# hw6.net
KiCad netlist of a schematic drawn in EAGLE
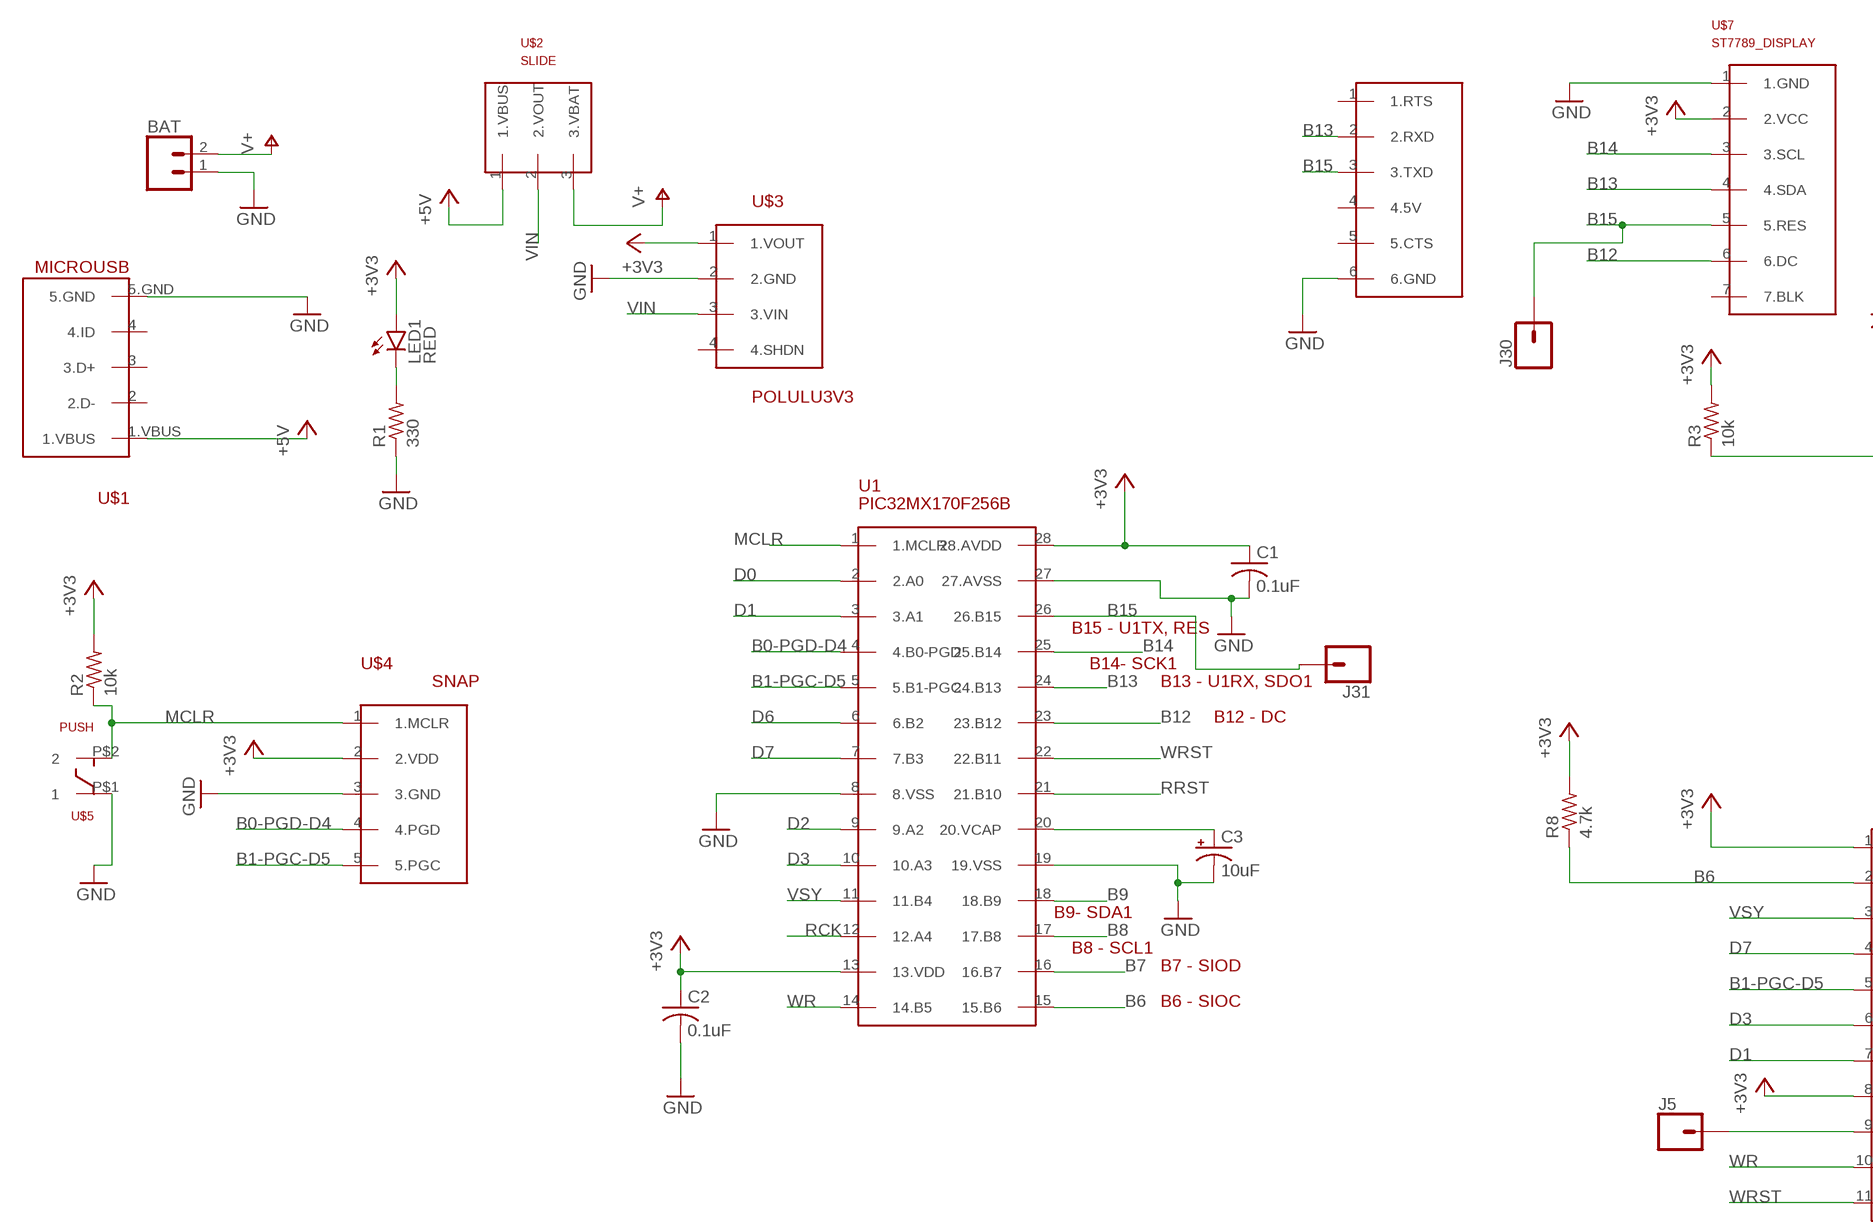
[diagram p0: schematic, sheet 1, part 1 of 2]
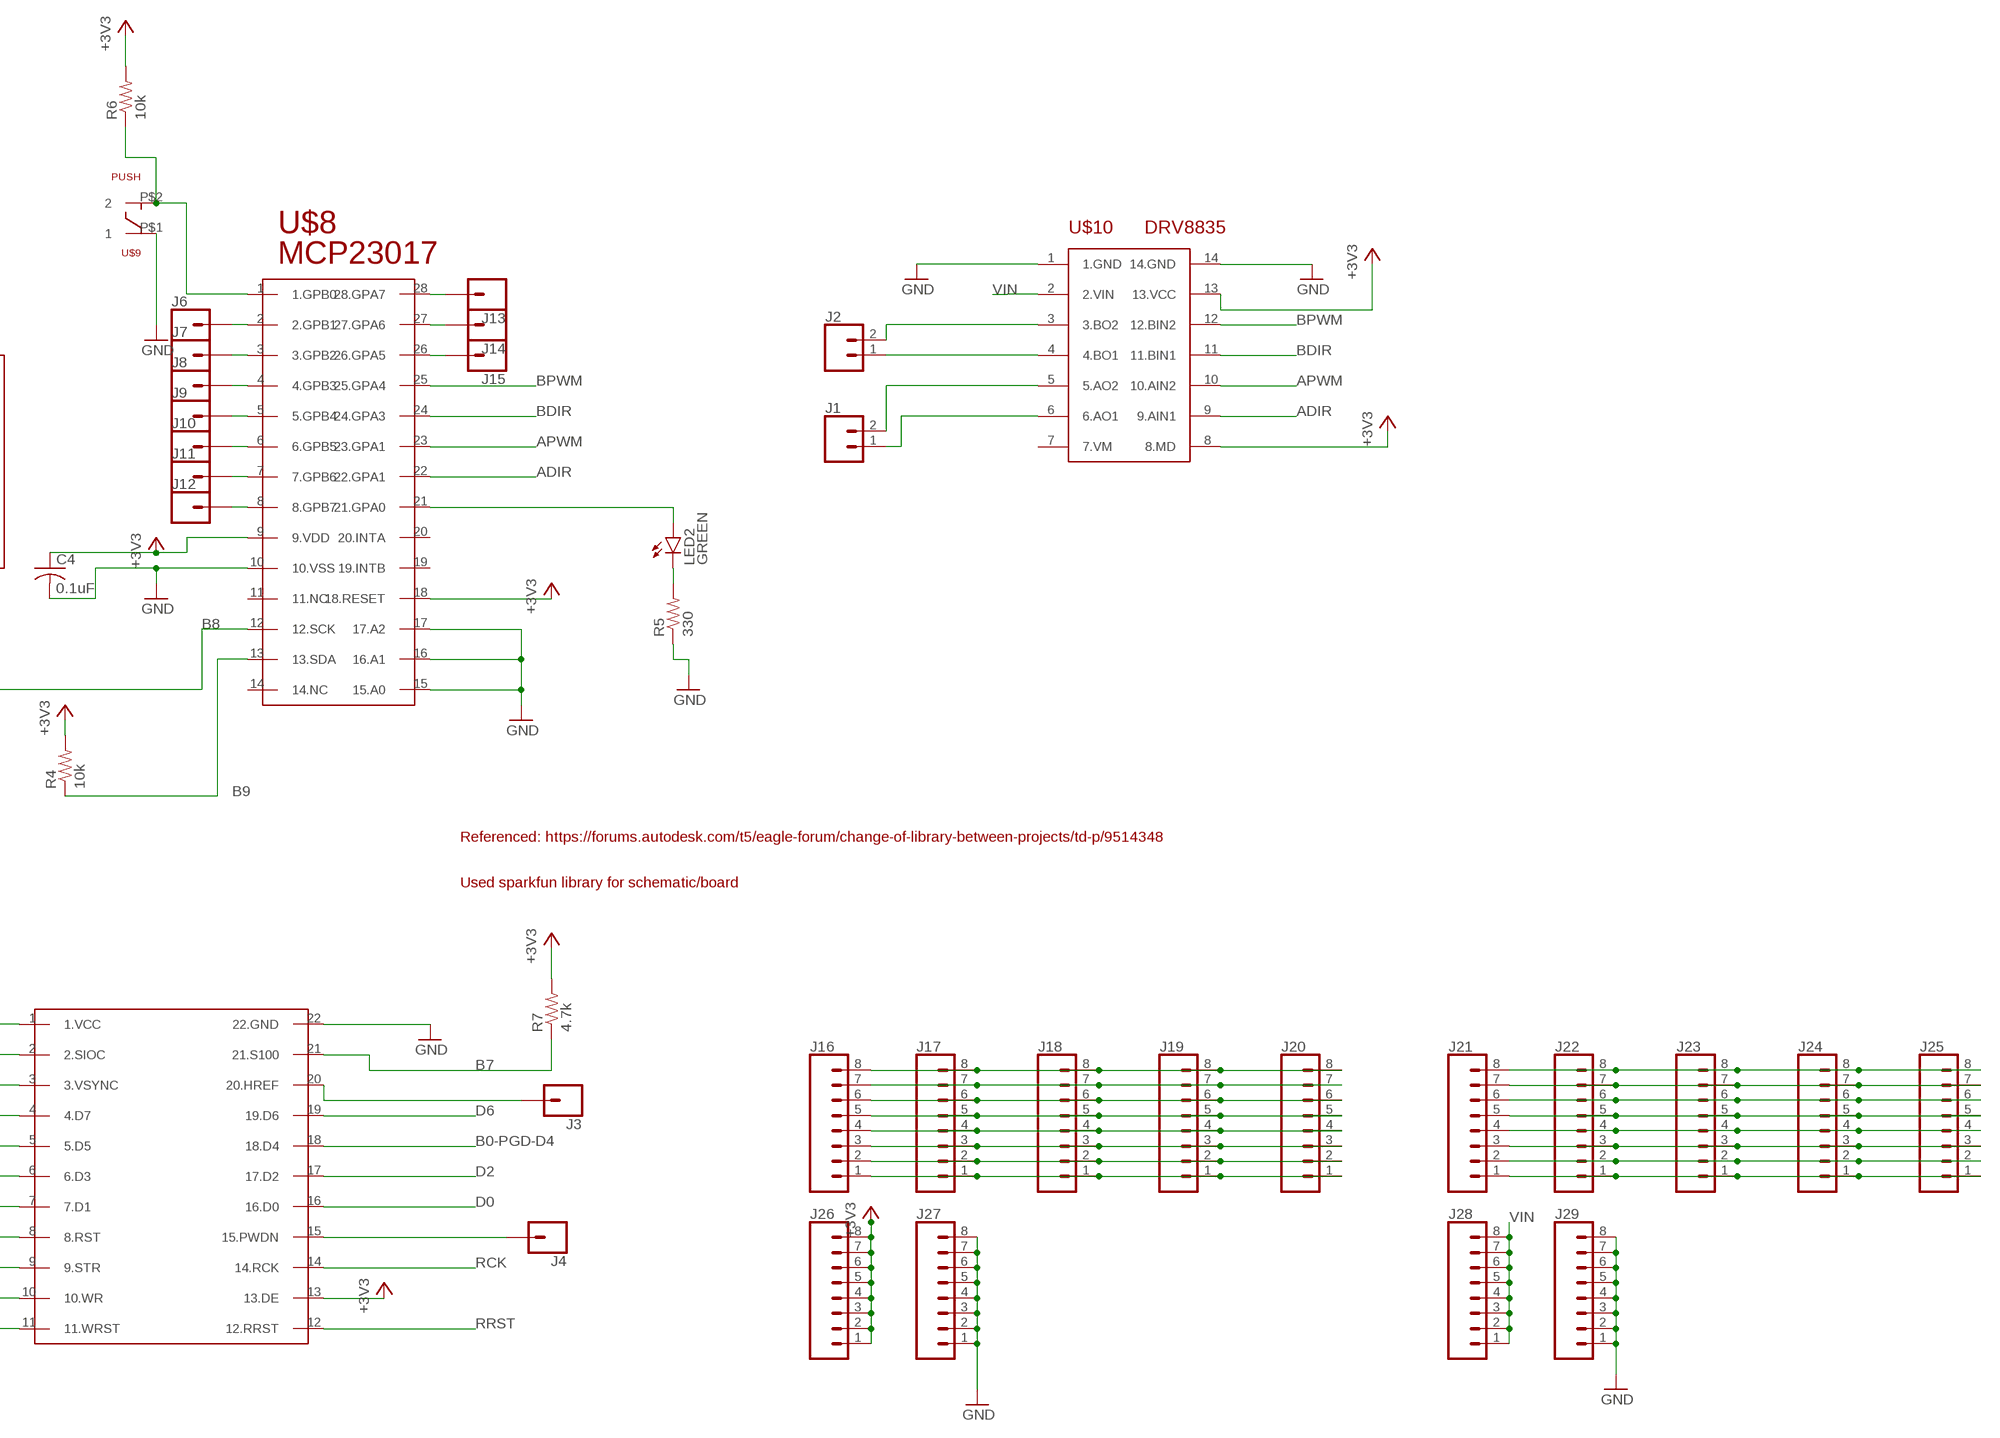
[diagram p1: schematic, sheet 1, part 2 of 2]

(export (version "E")
  (design (tool "Eeschema 10.0.6"))
  (components
    (comp (ref "BAT")
      (value "CONN_02")
      (footprint "eagle-import:1X02")
      (libsource (lib "eagle-import") (part "CONN_02"))
    )
    (comp (ref "C1")
      (value "0.1uF")
      (footprint "eagle-import:C025-030X050")
      (libsource (lib "eagle-import") (part "C-US025-030X050"))
    )
    (comp (ref "C2")
      (value "0.1uF")
      (footprint "eagle-import:C025-030X050")
      (libsource (lib "eagle-import") (part "C-US025-030X050"))
    )
    (comp (ref "C3")
      (value "10uF")
      (footprint "eagle-import:B45181B")
      (libsource (lib "eagle-import") (part "CPOL-USB45181B"))
    )
    (comp (ref "C4")
      (value "0.1uF")
      (footprint "eagle-import:C025-030X050")
      (libsource (lib "eagle-import") (part "C-US025-030X050"))
    )
    (comp (ref "J1")
      (value "CONN_02")
      (footprint "eagle-import:1X02")
      (libsource (lib "eagle-import") (part "CONN_02"))
    )
    (comp (ref "J2")
      (value "CONN_02")
      (footprint "eagle-import:1X02")
      (libsource (lib "eagle-import") (part "CONN_02"))
    )
    (comp (ref "J3")
      (value "CONN_01")
      (footprint "eagle-import:1X01")
      (libsource (lib "eagle-import") (part "CONN_01"))
    )
    (comp (ref "J4")
      (value "CONN_01")
      (footprint "eagle-import:1X01")
      (libsource (lib "eagle-import") (part "CONN_01"))
    )
    (comp (ref "J5")
      (value "CONN_01")
      (footprint "eagle-import:1X01")
      (libsource (lib "eagle-import") (part "CONN_01"))
    )
    (comp (ref "J6")
      (value "CONN_01")
      (footprint "eagle-import:1X01")
      (libsource (lib "eagle-import") (part "CONN_01"))
    )
    (comp (ref "J7")
      (value "CONN_01")
      (footprint "eagle-import:1X01")
      (libsource (lib "eagle-import") (part "CONN_01"))
    )
    (comp (ref "J8")
      (value "CONN_01")
      (footprint "eagle-import:1X01")
      (libsource (lib "eagle-import") (part "CONN_01"))
    )
    (comp (ref "J9")
      (value "CONN_01")
      (footprint "eagle-import:1X01")
      (libsource (lib "eagle-import") (part "CONN_01"))
    )
    (comp (ref "J10")
      (value "CONN_01")
      (footprint "eagle-import:1X01")
      (libsource (lib "eagle-import") (part "CONN_01"))
    )
    (comp (ref "J11")
      (value "CONN_01")
      (footprint "eagle-import:1X01")
      (libsource (lib "eagle-import") (part "CONN_01"))
    )
    (comp (ref "J12")
      (value "CONN_01")
      (footprint "eagle-import:1X01")
      (libsource (lib "eagle-import") (part "CONN_01"))
    )
    (comp (ref "J13")
      (value "CONN_01")
      (footprint "eagle-import:1X01")
      (libsource (lib "eagle-import") (part "CONN_01"))
    )
    (comp (ref "J14")
      (value "CONN_01")
      (footprint "eagle-import:1X01")
      (libsource (lib "eagle-import") (part "CONN_01"))
    )
    (comp (ref "J15")
      (value "CONN_01")
      (footprint "eagle-import:1X01")
      (libsource (lib "eagle-import") (part "CONN_01"))
    )
    (comp (ref "J16")
      (value "CONN_08\"")
      (footprint "eagle-import:1X08")
      (libsource (lib "eagle-import") (part "CONN_08{dblquote}"))
    )
    (comp (ref "J17")
      (value "CONN_08\"")
      (footprint "eagle-import:1X08")
      (libsource (lib "eagle-import") (part "CONN_08{dblquote}"))
    )
    (comp (ref "J18")
      (value "CONN_08\"")
      (footprint "eagle-import:1X08")
      (libsource (lib "eagle-import") (part "CONN_08{dblquote}"))
    )
    (comp (ref "J19")
      (value "CONN_08\"")
      (footprint "eagle-import:1X08")
      (libsource (lib "eagle-import") (part "CONN_08{dblquote}"))
    )
    (comp (ref "J20")
      (value "CONN_08\"")
      (footprint "eagle-import:1X08")
      (libsource (lib "eagle-import") (part "CONN_08{dblquote}"))
    )
    (comp (ref "J21")
      (value "CONN_08\"")
      (footprint "eagle-import:1X08")
      (libsource (lib "eagle-import") (part "CONN_08{dblquote}"))
    )
    (comp (ref "J22")
      (value "CONN_08\"")
      (footprint "eagle-import:1X08")
      (libsource (lib "eagle-import") (part "CONN_08{dblquote}"))
    )
    (comp (ref "J23")
      (value "CONN_08\"")
      (footprint "eagle-import:1X08")
      (libsource (lib "eagle-import") (part "CONN_08{dblquote}"))
    )
    (comp (ref "J24")
      (value "CONN_08\"")
      (footprint "eagle-import:1X08")
      (libsource (lib "eagle-import") (part "CONN_08{dblquote}"))
    )
    (comp (ref "J25")
      (value "CONN_08\"")
      (footprint "eagle-import:1X08")
      (libsource (lib "eagle-import") (part "CONN_08{dblquote}"))
    )
    (comp (ref "J26")
      (value "CONN_08\"")
      (footprint "eagle-import:1X08")
      (libsource (lib "eagle-import") (part "CONN_08{dblquote}"))
    )
    (comp (ref "J27")
      (value "CONN_08\"")
      (footprint "eagle-import:1X08")
      (libsource (lib "eagle-import") (part "CONN_08{dblquote}"))
    )
    (comp (ref "J28")
      (value "CONN_08\"")
      (footprint "eagle-import:1X08")
      (libsource (lib "eagle-import") (part "CONN_08{dblquote}"))
    )
    (comp (ref "J29")
      (value "CONN_08\"")
      (footprint "eagle-import:1X08")
      (libsource (lib "eagle-import") (part "CONN_08{dblquote}"))
    )
    (comp (ref "J30")
      (value "CONN_01")
      (footprint "eagle-import:1X01")
      (libsource (lib "eagle-import") (part "CONN_01"))
    )
    (comp (ref "J31")
      (value "CONN_01")
      (footprint "eagle-import:1X01")
      (libsource (lib "eagle-import") (part "CONN_01"))
    )
    (comp (ref "LED1")
      (value "RED")
      (footprint "eagle-import:LED3MM")
      (libsource (lib "eagle-import") (part "LED3MM"))
    )
    (comp (ref "LED2")
      (value "GREEN")
      (footprint "eagle-import:LED3MM")
      (libsource (lib "eagle-import") (part "LED3MM"))
    )
    (comp (ref "R1")
      (value "330")
      (footprint "eagle-import:0207_10")
      (libsource (lib "eagle-import") (part "R-US_0207/10"))
    )
    (comp (ref "R2")
      (value "10k")
      (footprint "eagle-import:0207_10")
      (libsource (lib "eagle-import") (part "R-US_0207/10"))
    )
    (comp (ref "R3")
      (value "10k")
      (footprint "eagle-import:0207_10")
      (libsource (lib "eagle-import") (part "R-US_0207/10"))
    )
    (comp (ref "R4")
      (value "10k")
      (footprint "eagle-import:0207_10")
      (libsource (lib "eagle-import") (part "R-US_0207/10"))
    )
    (comp (ref "R5")
      (value "330")
      (footprint "eagle-import:0207_10")
      (libsource (lib "eagle-import") (part "R-US_0207/10"))
    )
    (comp (ref "R6")
      (value "10k")
      (footprint "eagle-import:0207_10")
      (libsource (lib "eagle-import") (part "R-US_0207/10"))
    )
    (comp (ref "R7")
      (value "4.7k")
      (footprint "eagle-import:0207_10")
      (libsource (lib "eagle-import") (part "R-US_0207/10"))
    )
    (comp (ref "R8")
      (value "4.7k")
      (footprint "eagle-import:0207_10")
      (libsource (lib "eagle-import") (part "R-US_0207/10"))
    )
    (comp (ref "U$1")
      (value "MICROUSB")
      (footprint "eagle-import:MICROUSB1")
      (libsource (lib "eagle-import") (part "MICROUSB"))
    )
    (comp (ref "U$2")
      (value "SLIDE")
      (footprint "eagle-import:SLIDE")
      (libsource (lib "eagle-import") (part "SLIDE"))
    )
    (comp (ref "U$3")
      (value "POLULU3V3")
      (footprint "eagle-import:POLULU3V3")
      (libsource (lib "eagle-import") (part "POLULU3V3"))
    )
    (comp (ref "U$4")
      (value "SNAP")
      (footprint "eagle-import:SNAP")
      (libsource (lib "eagle-import") (part "SNAP"))
    )
    (comp (ref "U$5")
      (value "PUSH")
      (footprint "eagle-import:PUSH")
      (libsource (lib "eagle-import") (part "PUSH"))
    )
    (comp (ref "U$6")
      (value "USB2UART")
      (footprint "eagle-import:USB2UART")
      (libsource (lib "eagle-import") (part "USB2UART"))
    )
    (comp (ref "U$7")
      (value "ST7789_DISPLAY")
      (footprint "eagle-import:ST7789_DISPLAY")
      (libsource (lib "eagle-import") (part "ST7789_DISPLAY"))
    )
    (comp (ref "U$8")
      (value "MCP23017")
      (footprint "eagle-import:MCP23017")
      (libsource (lib "eagle-import") (part "MCP23017"))
    )
    (comp (ref "U$9")
      (value "PUSH")
      (footprint "eagle-import:PUSH")
      (libsource (lib "eagle-import") (part "PUSH"))
    )
    (comp (ref "U$10")
      (value "DRV8835")
      (footprint "eagle-import:DRV8835")
      (libsource (lib "eagle-import") (part "DRV8835"))
    )
    (comp (ref "U$11")
      (value "OV7670_CAMERA")
      (footprint "eagle-import:OV7870_CAMERA")
      (libsource (lib "eagle-import") (part "OV7670_CAMERA"))
    )
    (comp (ref "U1")
      (value "PIC32MX170F256B")
      (footprint "eagle-import:DIL28-3")
      (libsource (lib "eagle-import") (part "PIC32MX170F256B"))
    )
  )
  (nets
    (net (code "1") (name "+3V3") (class "Default")
      (node (ref "C1") (pin "1") (pinfunction "1_1") (pintype "passive"))
      (node (ref "C2") (pin "1") (pinfunction "1_1") (pintype "passive"))
      (node (ref "C4") (pin "1") (pinfunction "1_1") (pintype "passive"))
      (node (ref "J26") (pin "1") (pinfunction "1_1") (pintype "passive"))
      (node (ref "J26") (pin "2") (pinfunction "2_2") (pintype "passive"))
      (node (ref "J26") (pin "3") (pinfunction "3_3") (pintype "passive"))
      (node (ref "J26") (pin "4") (pinfunction "4_4") (pintype "passive"))
      (node (ref "J26") (pin "5") (pinfunction "5_5") (pintype "passive"))
      (node (ref "J26") (pin "6") (pinfunction "6_6") (pintype "passive"))
      (node (ref "J26") (pin "7") (pinfunction "7_7") (pintype "passive"))
      (node (ref "J26") (pin "8") (pinfunction "8_8") (pintype "passive"))
      (node (ref "LED1") (pin "A") (pinfunction "A_A") (pintype "passive"))
      (node (ref "R2") (pin "2") (pinfunction "2_2") (pintype "passive"))
      (node (ref "R3") (pin "2") (pinfunction "2_2") (pintype "passive"))
      (node (ref "R4") (pin "2") (pinfunction "2_2") (pintype "passive"))
      (node (ref "R6") (pin "2") (pinfunction "2_2") (pintype "passive"))
      (node (ref "R7") (pin "2") (pinfunction "2_2") (pintype "passive"))
      (node (ref "R8") (pin "2") (pinfunction "2_2") (pintype "passive"))
      (node (ref "U$10") (pin "13") (pinfunction "13.VCC_13") (pintype "bidirectional"))
      (node (ref "U$10") (pin "8") (pinfunction "8.MD_8") (pintype "bidirectional"))
      (node (ref "U$11") (pin "1") (pinfunction "1.VCC_1") (pintype "bidirectional"))
      (node (ref "U$11") (pin "13") (pinfunction "13.DE_13") (pintype "bidirectional"))
      (node (ref "U$11") (pin "8") (pinfunction "8.RST_8") (pintype "bidirectional"))
      (node (ref "U$3") (pin "1") (pinfunction "1.VOUT_1") (pintype "bidirectional"))
      (node (ref "U$4") (pin "2") (pinfunction "2.VDD_2") (pintype "bidirectional"))
      (node (ref "U$7") (pin "2") (pinfunction "2.VCC_2") (pintype "bidirectional"))
      (node (ref "U$8") (pin "18") (pinfunction "18.RESET_18") (pintype "bidirectional"))
      (node (ref "U$8") (pin "9") (pinfunction "9.VDD_9") (pintype "bidirectional"))
      (node (ref "U1") (pin "13") (pinfunction "13.VDD_13") (pintype "bidirectional"))
      (node (ref "U1") (pin "28") (pinfunction "28.AVDD_28") (pintype "bidirectional"))
    )
    (net (code "2") (name "+5V") (class "Default")
      (node (ref "U$1") (pin "1.VBUS") (pinfunction "1.VBUS_1.VBUS") (pintype "bidirectional"))
      (node (ref "U$2") (pin "1") (pinfunction "1.VBUS_1") (pintype "bidirectional"))
    )
    (net (code "3") (name "/ADIR") (class "Default")
      (node (ref "U$10") (pin "9") (pinfunction "9.AIN1_9") (pintype "bidirectional"))
      (node (ref "U$8") (pin "22") (pinfunction "22.GPA1_22") (pintype "bidirectional"))
    )
    (net (code "4") (name "/APWM") (class "Default")
      (node (ref "U$10") (pin "10") (pinfunction "10.AIN2_10") (pintype "bidirectional"))
      (node (ref "U$8") (pin "23") (pinfunction "23.GPA1_23") (pintype "bidirectional"))
    )
    (net (code "5") (name "/B0-PGD-D4") (class "Default")
      (node (ref "U$11") (pin "18") (pinfunction "18.D4_18") (pintype "bidirectional"))
      (node (ref "U$4") (pin "4") (pinfunction "4.PGD_4") (pintype "bidirectional"))
      (node (ref "U1") (pin "4") (pinfunction "4.B0-PGD_4") (pintype "bidirectional"))
    )
    (net (code "6") (name "/B1-PGC-D5") (class "Default")
      (node (ref "U$11") (pin "5") (pinfunction "5.D5_5") (pintype "bidirectional"))
      (node (ref "U$4") (pin "5") (pinfunction "5.PGC_5") (pintype "bidirectional"))
      (node (ref "U1") (pin "5") (pinfunction "5.B1-PGC_5") (pintype "bidirectional"))
    )
    (net (code "7") (name "/B6") (class "Default")
      (node (ref "R8") (pin "1") (pinfunction "1_1") (pintype "passive"))
      (node (ref "U$11") (pin "2") (pinfunction "2.SIOC_2") (pintype "bidirectional"))
      (node (ref "U1") (pin "15") (pinfunction "15.B6_15") (pintype "bidirectional"))
    )
    (net (code "8") (name "/B7") (class "Default")
      (node (ref "R7") (pin "1") (pinfunction "1_1") (pintype "passive"))
      (node (ref "U$11") (pin "21") (pinfunction "21.S100_21") (pintype "bidirectional"))
      (node (ref "U1") (pin "16") (pinfunction "16.B7_16") (pintype "bidirectional"))
    )
    (net (code "9") (name "/B8") (class "Default")
      (node (ref "R3") (pin "1") (pinfunction "1_1") (pintype "passive"))
      (node (ref "U$8") (pin "12") (pinfunction "12.SCK_12") (pintype "bidirectional"))
      (node (ref "U1") (pin "17") (pinfunction "17.B8_17") (pintype "bidirectional"))
    )
    (net (code "10") (name "/B9") (class "Default")
      (node (ref "R4") (pin "1") (pinfunction "1_1") (pintype "passive"))
      (node (ref "U$8") (pin "13") (pinfunction "13.SDA_13") (pintype "bidirectional"))
      (node (ref "U1") (pin "18") (pinfunction "18.B9_18") (pintype "bidirectional"))
    )
    (net (code "11") (name "/B12") (class "Default")
      (node (ref "U$7") (pin "6") (pinfunction "6.DC_6") (pintype "bidirectional"))
      (node (ref "U1") (pin "23") (pinfunction "23.B12_23") (pintype "bidirectional"))
    )
    (net (code "12") (name "/B13") (class "Default")
      (node (ref "U$6") (pin "2") (pinfunction "2.RXD_2") (pintype "bidirectional"))
      (node (ref "U$7") (pin "4") (pinfunction "4.SDA_4") (pintype "bidirectional"))
      (node (ref "U1") (pin "24") (pinfunction "24.B13_24") (pintype "bidirectional"))
    )
    (net (code "13") (name "/B14") (class "Default")
      (node (ref "U$7") (pin "3") (pinfunction "3.SCL_3") (pintype "bidirectional"))
      (node (ref "U1") (pin "25") (pinfunction "25.B14_25") (pintype "bidirectional"))
    )
    (net (code "14") (name "/B15") (class "Default")
      (node (ref "J30") (pin "1") (pinfunction "1_1") (pintype "passive"))
      (node (ref "J31") (pin "1") (pinfunction "1_1") (pintype "passive"))
      (node (ref "U$6") (pin "3") (pinfunction "3.TXD_3") (pintype "bidirectional"))
      (node (ref "U$7") (pin "5") (pinfunction "5.RES_5") (pintype "bidirectional"))
      (node (ref "U1") (pin "26") (pinfunction "26.B15_26") (pintype "bidirectional"))
    )
    (net (code "15") (name "/BDIR") (class "Default")
      (node (ref "U$10") (pin "11") (pinfunction "11.BIN1_11") (pintype "bidirectional"))
      (node (ref "U$8") (pin "24") (pinfunction "24.GPA3_24") (pintype "bidirectional"))
    )
    (net (code "16") (name "/BPWM") (class "Default")
      (node (ref "U$10") (pin "12") (pinfunction "12.BIN2_12") (pintype "bidirectional"))
      (node (ref "U$8") (pin "25") (pinfunction "25.GPA4_25") (pintype "bidirectional"))
    )
    (net (code "17") (name "/D0") (class "Default")
      (node (ref "U$11") (pin "16") (pinfunction "16.D0_16") (pintype "bidirectional"))
      (node (ref "U1") (pin "2") (pinfunction "2.A0_2") (pintype "bidirectional"))
    )
    (net (code "18") (name "/D1") (class "Default")
      (node (ref "U$11") (pin "7") (pinfunction "7.D1_7") (pintype "bidirectional"))
      (node (ref "U1") (pin "3") (pinfunction "3.A1_3") (pintype "bidirectional"))
    )
    (net (code "19") (name "/D2") (class "Default")
      (node (ref "U$11") (pin "17") (pinfunction "17.D2_17") (pintype "bidirectional"))
      (node (ref "U1") (pin "9") (pinfunction "9.A2_9") (pintype "bidirectional"))
    )
    (net (code "20") (name "/D3") (class "Default")
      (node (ref "U$11") (pin "6") (pinfunction "6.D3_6") (pintype "bidirectional"))
      (node (ref "U1") (pin "10") (pinfunction "10.A3_10") (pintype "bidirectional"))
    )
    (net (code "21") (name "/D6") (class "Default")
      (node (ref "U$11") (pin "19") (pinfunction "19.D6_19") (pintype "bidirectional"))
      (node (ref "U1") (pin "6") (pinfunction "6.B2_6") (pintype "bidirectional"))
    )
    (net (code "22") (name "/D7") (class "Default")
      (node (ref "U$11") (pin "4") (pinfunction "4.D7_4") (pintype "bidirectional"))
      (node (ref "U1") (pin "7") (pinfunction "7.B3_7") (pintype "bidirectional"))
    )
    (net (code "23") (name "/MCLR") (class "Default")
      (node (ref "R2") (pin "1") (pinfunction "1_1") (pintype "passive"))
      (node (ref "U$4") (pin "1") (pinfunction "1.MCLR_1") (pintype "bidirectional"))
      (node (ref "U$5") (pin "P$2") (pinfunction "2_P$2") (pintype "bidirectional"))
      (node (ref "U1") (pin "1") (pinfunction "1.MCLR_1") (pintype "bidirectional"))
    )
    (net (code "24") (name "/RCK") (class "Default")
      (node (ref "U$11") (pin "14") (pinfunction "14.RCK_14") (pintype "bidirectional"))
      (node (ref "U1") (pin "12") (pinfunction "12.A4_12") (pintype "bidirectional"))
    )
    (net (code "25") (name "/RRST") (class "Default")
      (node (ref "U$11") (pin "12") (pinfunction "12.RRST_12") (pintype "bidirectional"))
      (node (ref "U1") (pin "21") (pinfunction "21.B10_21") (pintype "bidirectional"))
    )
    (net (code "26") (name "/VIN") (class "Default")
      (node (ref "J28") (pin "1") (pinfunction "1_1") (pintype "passive"))
      (node (ref "J28") (pin "2") (pinfunction "2_2") (pintype "passive"))
      (node (ref "J28") (pin "3") (pinfunction "3_3") (pintype "passive"))
      (node (ref "J28") (pin "4") (pinfunction "4_4") (pintype "passive"))
      (node (ref "J28") (pin "5") (pinfunction "5_5") (pintype "passive"))
      (node (ref "J28") (pin "6") (pinfunction "6_6") (pintype "passive"))
      (node (ref "J28") (pin "7") (pinfunction "7_7") (pintype "passive"))
      (node (ref "J28") (pin "8") (pinfunction "8_8") (pintype "passive"))
      (node (ref "U$10") (pin "2") (pinfunction "2.VIN_2") (pintype "bidirectional"))
      (node (ref "U$2") (pin "2") (pinfunction "2.VOUT_2") (pintype "bidirectional"))
      (node (ref "U$3") (pin "3") (pinfunction "3.VIN_3") (pintype "bidirectional"))
    )
    (net (code "27") (name "/VSY") (class "Default")
      (node (ref "U$11") (pin "3") (pinfunction "3.VSYNC_3") (pintype "bidirectional"))
      (node (ref "U1") (pin "11") (pinfunction "11.B4_11") (pintype "bidirectional"))
    )
    (net (code "28") (name "/WR") (class "Default")
      (node (ref "U$11") (pin "10") (pinfunction "10.WR_10") (pintype "bidirectional"))
      (node (ref "U1") (pin "14") (pinfunction "14.B5_14") (pintype "bidirectional"))
    )
    (net (code "29") (name "/WRST") (class "Default")
      (node (ref "U$11") (pin "11") (pinfunction "11.WRST_11") (pintype "bidirectional"))
      (node (ref "U1") (pin "22") (pinfunction "22.B11_22") (pintype "bidirectional"))
    )
    (net (code "30") (name "GND") (class "Default")
      (node (ref "BAT") (pin "1") (pinfunction "1_1") (pintype "passive"))
      (node (ref "C1") (pin "2") (pinfunction "2_2") (pintype "passive"))
      (node (ref "C2") (pin "2") (pinfunction "2_2") (pintype "passive"))
      (node (ref "C3") (pin "-") (pinfunction "-_-") (pintype "passive"))
      (node (ref "C4") (pin "2") (pinfunction "2_2") (pintype "passive"))
      (node (ref "J27") (pin "1") (pinfunction "1_1") (pintype "passive"))
      (node (ref "J27") (pin "2") (pinfunction "2_2") (pintype "passive"))
      (node (ref "J27") (pin "3") (pinfunction "3_3") (pintype "passive"))
      (node (ref "J27") (pin "4") (pinfunction "4_4") (pintype "passive"))
      (node (ref "J27") (pin "5") (pinfunction "5_5") (pintype "passive"))
      (node (ref "J27") (pin "6") (pinfunction "6_6") (pintype "passive"))
      (node (ref "J27") (pin "7") (pinfunction "7_7") (pintype "passive"))
      (node (ref "J27") (pin "8") (pinfunction "8_8") (pintype "passive"))
      (node (ref "J29") (pin "1") (pinfunction "1_1") (pintype "passive"))
      (node (ref "J29") (pin "2") (pinfunction "2_2") (pintype "passive"))
      (node (ref "J29") (pin "3") (pinfunction "3_3") (pintype "passive"))
      (node (ref "J29") (pin "4") (pinfunction "4_4") (pintype "passive"))
      (node (ref "J29") (pin "5") (pinfunction "5_5") (pintype "passive"))
      (node (ref "J29") (pin "6") (pinfunction "6_6") (pintype "passive"))
      (node (ref "J29") (pin "7") (pinfunction "7_7") (pintype "passive"))
      (node (ref "J29") (pin "8") (pinfunction "8_8") (pintype "passive"))
      (node (ref "R1") (pin "1") (pinfunction "1_1") (pintype "passive"))
      (node (ref "R5") (pin "1") (pinfunction "1_1") (pintype "passive"))
      (node (ref "U$1") (pin "5.GND") (pinfunction "5.GND_5.GND") (pintype "bidirectional"))
      (node (ref "U$10") (pin "1") (pinfunction "1.GND_1") (pintype "bidirectional"))
      (node (ref "U$10") (pin "14") (pinfunction "14.GND_14") (pintype "bidirectional"))
      (node (ref "U$11") (pin "22") (pinfunction "22.GND_22") (pintype "bidirectional"))
      (node (ref "U$3") (pin "2") (pinfunction "2.GND_2") (pintype "bidirectional"))
      (node (ref "U$4") (pin "3") (pinfunction "3.GND_3") (pintype "bidirectional"))
      (node (ref "U$5") (pin "P$1") (pinfunction "1_P$1") (pintype "bidirectional"))
      (node (ref "U$6") (pin "6") (pinfunction "6.GND_6") (pintype "bidirectional"))
      (node (ref "U$7") (pin "1") (pinfunction "1.GND_1") (pintype "bidirectional"))
      (node (ref "U$8") (pin "10") (pinfunction "10.VSS_10") (pintype "bidirectional"))
      (node (ref "U$8") (pin "15") (pinfunction "15.A0_15") (pintype "bidirectional"))
      (node (ref "U$8") (pin "16") (pinfunction "16.A1_16") (pintype "bidirectional"))
      (node (ref "U$8") (pin "17") (pinfunction "17.A2_17") (pintype "bidirectional"))
      (node (ref "U$9") (pin "P$1") (pinfunction "1_P$1") (pintype "bidirectional"))
      (node (ref "U1") (pin "19") (pinfunction "19.VSS_19") (pintype "bidirectional"))
      (node (ref "U1") (pin "27") (pinfunction "27.AVSS_27") (pintype "bidirectional"))
      (node (ref "U1") (pin "8") (pinfunction "8.VSS_8") (pintype "bidirectional"))
    )
    (net (code "31") (name "Net-(J16-Pad1)") (class "Default")
      (node (ref "J16") (pin "1") (pinfunction "1_1") (pintype "passive"))
      (node (ref "J17") (pin "1") (pinfunction "1_1") (pintype "passive"))
      (node (ref "J18") (pin "1") (pinfunction "1_1") (pintype "passive"))
      (node (ref "J19") (pin "1") (pinfunction "1_1") (pintype "passive"))
      (node (ref "J20") (pin "1") (pinfunction "1_1") (pintype "passive"))
    )
    (net (code "32") (name "Net-(J16-Pad2)") (class "Default")
      (node (ref "J16") (pin "2") (pinfunction "2_2") (pintype "passive"))
      (node (ref "J17") (pin "2") (pinfunction "2_2") (pintype "passive"))
      (node (ref "J18") (pin "2") (pinfunction "2_2") (pintype "passive"))
      (node (ref "J19") (pin "2") (pinfunction "2_2") (pintype "passive"))
      (node (ref "J20") (pin "2") (pinfunction "2_2") (pintype "passive"))
    )
    (net (code "33") (name "Net-(J16-Pad3)") (class "Default")
      (node (ref "J16") (pin "3") (pinfunction "3_3") (pintype "passive"))
      (node (ref "J17") (pin "3") (pinfunction "3_3") (pintype "passive"))
      (node (ref "J18") (pin "3") (pinfunction "3_3") (pintype "passive"))
      (node (ref "J19") (pin "3") (pinfunction "3_3") (pintype "passive"))
      (node (ref "J20") (pin "3") (pinfunction "3_3") (pintype "passive"))
    )
    (net (code "34") (name "Net-(J16-Pad4)") (class "Default")
      (node (ref "J16") (pin "4") (pinfunction "4_4") (pintype "passive"))
      (node (ref "J17") (pin "4") (pinfunction "4_4") (pintype "passive"))
      (node (ref "J18") (pin "4") (pinfunction "4_4") (pintype "passive"))
      (node (ref "J19") (pin "4") (pinfunction "4_4") (pintype "passive"))
      (node (ref "J20") (pin "4") (pinfunction "4_4") (pintype "passive"))
    )
    (net (code "35") (name "Net-(J16-Pad5)") (class "Default")
      (node (ref "J16") (pin "5") (pinfunction "5_5") (pintype "passive"))
      (node (ref "J17") (pin "5") (pinfunction "5_5") (pintype "passive"))
      (node (ref "J18") (pin "5") (pinfunction "5_5") (pintype "passive"))
      (node (ref "J19") (pin "5") (pinfunction "5_5") (pintype "passive"))
      (node (ref "J20") (pin "5") (pinfunction "5_5") (pintype "passive"))
    )
    (net (code "36") (name "Net-(J16-Pad6)") (class "Default")
      (node (ref "J16") (pin "6") (pinfunction "6_6") (pintype "passive"))
      (node (ref "J17") (pin "6") (pinfunction "6_6") (pintype "passive"))
      (node (ref "J18") (pin "6") (pinfunction "6_6") (pintype "passive"))
      (node (ref "J19") (pin "6") (pinfunction "6_6") (pintype "passive"))
      (node (ref "J20") (pin "6") (pinfunction "6_6") (pintype "passive"))
    )
    (net (code "37") (name "Net-(J16-Pad7)") (class "Default")
      (node (ref "J16") (pin "7") (pinfunction "7_7") (pintype "passive"))
      (node (ref "J17") (pin "7") (pinfunction "7_7") (pintype "passive"))
      (node (ref "J18") (pin "7") (pinfunction "7_7") (pintype "passive"))
      (node (ref "J19") (pin "7") (pinfunction "7_7") (pintype "passive"))
      (node (ref "J20") (pin "7") (pinfunction "7_7") (pintype "passive"))
    )
    (net (code "38") (name "Net-(J16-Pad8)") (class "Default")
      (node (ref "J16") (pin "8") (pinfunction "8_8") (pintype "passive"))
      (node (ref "J17") (pin "8") (pinfunction "8_8") (pintype "passive"))
      (node (ref "J18") (pin "8") (pinfunction "8_8") (pintype "passive"))
      (node (ref "J19") (pin "8") (pinfunction "8_8") (pintype "passive"))
      (node (ref "J20") (pin "8") (pinfunction "8_8") (pintype "passive"))
    )
    (net (code "39") (name "Net-(J21-Pad1)") (class "Default")
      (node (ref "J21") (pin "1") (pinfunction "1_1") (pintype "passive"))
      (node (ref "J22") (pin "1") (pinfunction "1_1") (pintype "passive"))
      (node (ref "J23") (pin "1") (pinfunction "1_1") (pintype "passive"))
      (node (ref "J24") (pin "1") (pinfunction "1_1") (pintype "passive"))
      (node (ref "J25") (pin "1") (pinfunction "1_1") (pintype "passive"))
    )
    (net (code "40") (name "Net-(J21-Pad2)") (class "Default")
      (node (ref "J21") (pin "2") (pinfunction "2_2") (pintype "passive"))
      (node (ref "J22") (pin "2") (pinfunction "2_2") (pintype "passive"))
      (node (ref "J23") (pin "2") (pinfunction "2_2") (pintype "passive"))
      (node (ref "J24") (pin "2") (pinfunction "2_2") (pintype "passive"))
      (node (ref "J25") (pin "2") (pinfunction "2_2") (pintype "passive"))
    )
    (net (code "41") (name "Net-(J21-Pad3)") (class "Default")
      (node (ref "J21") (pin "3") (pinfunction "3_3") (pintype "passive"))
      (node (ref "J22") (pin "3") (pinfunction "3_3") (pintype "passive"))
      (node (ref "J23") (pin "3") (pinfunction "3_3") (pintype "passive"))
      (node (ref "J24") (pin "3") (pinfunction "3_3") (pintype "passive"))
      (node (ref "J25") (pin "3") (pinfunction "3_3") (pintype "passive"))
    )
    (net (code "42") (name "Net-(J21-Pad4)") (class "Default")
      (node (ref "J21") (pin "4") (pinfunction "4_4") (pintype "passive"))
      (node (ref "J22") (pin "4") (pinfunction "4_4") (pintype "passive"))
      (node (ref "J23") (pin "4") (pinfunction "4_4") (pintype "passive"))
      (node (ref "J24") (pin "4") (pinfunction "4_4") (pintype "passive"))
      (node (ref "J25") (pin "4") (pinfunction "4_4") (pintype "passive"))
    )
    (net (code "43") (name "Net-(J21-Pad5)") (class "Default")
      (node (ref "J21") (pin "5") (pinfunction "5_5") (pintype "passive"))
      (node (ref "J22") (pin "5") (pinfunction "5_5") (pintype "passive"))
      (node (ref "J23") (pin "5") (pinfunction "5_5") (pintype "passive"))
      (node (ref "J24") (pin "5") (pinfunction "5_5") (pintype "passive"))
      (node (ref "J25") (pin "5") (pinfunction "5_5") (pintype "passive"))
    )
    (net (code "44") (name "Net-(J21-Pad6)") (class "Default")
      (node (ref "J21") (pin "6") (pinfunction "6_6") (pintype "passive"))
      (node (ref "J22") (pin "6") (pinfunction "6_6") (pintype "passive"))
      (node (ref "J23") (pin "6") (pinfunction "6_6") (pintype "passive"))
      (node (ref "J24") (pin "6") (pinfunction "6_6") (pintype "passive"))
      (node (ref "J25") (pin "6") (pinfunction "6_6") (pintype "passive"))
    )
    (net (code "45") (name "Net-(J21-Pad7)") (class "Default")
      (node (ref "J21") (pin "7") (pinfunction "7_7") (pintype "passive"))
      (node (ref "J22") (pin "7") (pinfunction "7_7") (pintype "passive"))
      (node (ref "J23") (pin "7") (pinfunction "7_7") (pintype "passive"))
      (node (ref "J24") (pin "7") (pinfunction "7_7") (pintype "passive"))
      (node (ref "J25") (pin "7") (pinfunction "7_7") (pintype "passive"))
    )
    (net (code "46") (name "Net-(J21-Pad8)") (class "Default")
      (node (ref "J21") (pin "8") (pinfunction "8_8") (pintype "passive"))
      (node (ref "J22") (pin "8") (pinfunction "8_8") (pintype "passive"))
      (node (ref "J23") (pin "8") (pinfunction "8_8") (pintype "passive"))
      (node (ref "J24") (pin "8") (pinfunction "8_8") (pintype "passive"))
      (node (ref "J25") (pin "8") (pinfunction "8_8") (pintype "passive"))
    )
    (net (code "47") (name "Net-(LED1-C)") (class "Default")
      (node (ref "LED1") (pin "K") (pinfunction "C_K") (pintype "passive"))
      (node (ref "R1") (pin "2") (pinfunction "2_2") (pintype "passive"))
    )
    (net (code "48") (name "Net-(LED2-C)") (class "Default")
      (node (ref "LED2") (pin "K") (pinfunction "C_K") (pintype "passive"))
      (node (ref "R5") (pin "2") (pinfunction "2_2") (pintype "passive"))
    )
    (net (code "49") (name "Net-(U$8-1.GPB0)") (class "Default")
      (node (ref "R6") (pin "1") (pinfunction "1_1") (pintype "passive"))
      (node (ref "U$8") (pin "1") (pinfunction "1.GPB0_1") (pintype "bidirectional"))
      (node (ref "U$9") (pin "P$2") (pinfunction "2_P$2") (pintype "bidirectional"))
    )
    (net (code "50") (name "Net-(U$8-2.GPB1)") (class "Default")
      (node (ref "J6") (pin "1") (pinfunction "1_1") (pintype "passive"))
      (node (ref "U$8") (pin "2") (pinfunction "2.GPB1_2") (pintype "bidirectional"))
    )
    (net (code "51") (name "Net-(U$8-3.GPB2)") (class "Default")
      (node (ref "J7") (pin "1") (pinfunction "1_1") (pintype "passive"))
      (node (ref "U$8") (pin "3") (pinfunction "3.GPB2_3") (pintype "bidirectional"))
    )
    (net (code "52") (name "Net-(U$8-4.GPB3)") (class "Default")
      (node (ref "J8") (pin "1") (pinfunction "1_1") (pintype "passive"))
      (node (ref "U$8") (pin "4") (pinfunction "4.GPB3_4") (pintype "bidirectional"))
    )
    (net (code "53") (name "Net-(U$8-5.GPB4)") (class "Default")
      (node (ref "J9") (pin "1") (pinfunction "1_1") (pintype "passive"))
      (node (ref "U$8") (pin "5") (pinfunction "5.GPB4_5") (pintype "bidirectional"))
    )
    (net (code "54") (name "Net-(U$8-6.GPB5)") (class "Default")
      (node (ref "J10") (pin "1") (pinfunction "1_1") (pintype "passive"))
      (node (ref "U$8") (pin "6") (pinfunction "6.GPB5_6") (pintype "bidirectional"))
    )
    (net (code "55") (name "Net-(U$8-7.GPB6)") (class "Default")
      (node (ref "J11") (pin "1") (pinfunction "1_1") (pintype "passive"))
      (node (ref "U$8") (pin "7") (pinfunction "7.GPB6_7") (pintype "bidirectional"))
    )
    (net (code "56") (name "Net-(U$8-8.GPB7)") (class "Default")
      (node (ref "J12") (pin "1") (pinfunction "1_1") (pintype "passive"))
      (node (ref "U$8") (pin "8") (pinfunction "8.GPB7_8") (pintype "bidirectional"))
    )
    (net (code "57") (name "Net-(U$8-21.GPA0)") (class "Default")
      (node (ref "LED2") (pin "A") (pinfunction "A_A") (pintype "passive"))
      (node (ref "U$8") (pin "21") (pinfunction "21.GPA0_21") (pintype "bidirectional"))
    )
    (net (code "58") (name "Net-(U$8-26.GPA5)") (class "Default")
      (node (ref "J15") (pin "1") (pinfunction "1_1") (pintype "passive"))
      (node (ref "U$8") (pin "26") (pinfunction "26.GPA5_26") (pintype "bidirectional"))
    )
    (net (code "59") (name "Net-(U$8-27.GPA6)") (class "Default")
      (node (ref "J14") (pin "1") (pinfunction "1_1") (pintype "passive"))
      (node (ref "U$8") (pin "27") (pinfunction "27.GPA6_27") (pintype "bidirectional"))
    )
    (net (code "60") (name "Net-(U$8-28.GPA7)") (class "Default")
      (node (ref "J13") (pin "1") (pinfunction "1_1") (pintype "passive"))
      (node (ref "U$8") (pin "28") (pinfunction "28.GPA7_28") (pintype "bidirectional"))
    )
    (net (code "61") (name "Net-(U$10-3.BO2)") (class "Default")
      (node (ref "J2") (pin "2") (pinfunction "2_2") (pintype "passive"))
      (node (ref "U$10") (pin "3") (pinfunction "3.BO2_3") (pintype "bidirectional"))
    )
    (net (code "62") (name "Net-(U$10-4.BO1)") (class "Default")
      (node (ref "J2") (pin "1") (pinfunction "1_1") (pintype "passive"))
      (node (ref "U$10") (pin "4") (pinfunction "4.BO1_4") (pintype "bidirectional"))
    )
    (net (code "63") (name "Net-(U$10-5.AO2)") (class "Default")
      (node (ref "J1") (pin "2") (pinfunction "2_2") (pintype "passive"))
      (node (ref "U$10") (pin "5") (pinfunction "5.AO2_5") (pintype "bidirectional"))
    )
    (net (code "64") (name "Net-(U$10-6.AO1)") (class "Default")
      (node (ref "J1") (pin "1") (pinfunction "1_1") (pintype "passive"))
      (node (ref "U$10") (pin "6") (pinfunction "6.AO1_6") (pintype "bidirectional"))
    )
    (net (code "65") (name "Net-(U$11-9.STR)") (class "Default")
      (node (ref "J5") (pin "1") (pinfunction "1_1") (pintype "passive"))
      (node (ref "U$11") (pin "9") (pinfunction "9.STR_9") (pintype "bidirectional"))
    )
    (net (code "66") (name "Net-(U$11-15.PWDN)") (class "Default")
      (node (ref "J4") (pin "1") (pinfunction "1_1") (pintype "passive"))
      (node (ref "U$11") (pin "15") (pinfunction "15.PWDN_15") (pintype "bidirectional"))
    )
    (net (code "67") (name "Net-(U$11-20.HREF)") (class "Default")
      (node (ref "J3") (pin "1") (pinfunction "1_1") (pintype "passive"))
      (node (ref "U$11") (pin "20") (pinfunction "20.HREF_20") (pintype "bidirectional"))
    )
    (net (code "68") (name "Net-(U1-20.VCAP)") (class "Default")
      (node (ref "C3") (pin "+") (pinfunction "+_+") (pintype "passive"))
      (node (ref "U1") (pin "20") (pinfunction "20.VCAP_20") (pintype "bidirectional"))
    )
    (net (code "69") (name "V+") (class "Default")
      (node (ref "BAT") (pin "2") (pinfunction "2_2") (pintype "passive"))
      (node (ref "U$2") (pin "3") (pinfunction "3.VBAT_3") (pintype "bidirectional"))
    )
    (net (code "70") (name "unconnected-(U$1-2.D--Pad2)") (class "Default")
      (node (ref "U$1") (pin "2") (pinfunction "2.D-_2") (pintype "bidirectional"))
    )
    (net (code "71") (name "unconnected-(U$1-3.D+-Pad3)") (class "Default")
      (node (ref "U$1") (pin "3") (pinfunction "3.D+_3") (pintype "bidirectional"))
    )
    (net (code "72") (name "unconnected-(U$1-4.ID-Pad4)") (class "Default")
      (node (ref "U$1") (pin "4") (pinfunction "4.ID_4") (pintype "bidirectional"))
    )
    (net (code "73") (name "unconnected-(U$3-4.SHDN-Pad4)") (class "Default")
      (node (ref "U$3") (pin "4") (pinfunction "4.SHDN_4") (pintype "bidirectional"))
    )
    (net (code "74") (name "unconnected-(U$6-1.RTS-Pad1)") (class "Default")
      (node (ref "U$6") (pin "1") (pinfunction "1.RTS_1") (pintype "bidirectional"))
    )
    (net (code "75") (name "unconnected-(U$6-4.5V-Pad4)") (class "Default")
      (node (ref "U$6") (pin "4") (pinfunction "4.5V_4") (pintype "bidirectional"))
    )
    (net (code "76") (name "unconnected-(U$6-5.CTS-Pad5)") (class "Default")
      (node (ref "U$6") (pin "5") (pinfunction "5.CTS_5") (pintype "bidirectional"))
    )
    (net (code "77") (name "unconnected-(U$7-7.BLK-Pad7)") (class "Default")
      (node (ref "U$7") (pin "7") (pinfunction "7.BLK_7") (pintype "bidirectional"))
    )
    (net (code "78") (name "unconnected-(U$8-11.NC-Pad11)") (class "Default")
      (node (ref "U$8") (pin "11") (pinfunction "11.NC_11") (pintype "bidirectional"))
    )
    (net (code "79") (name "unconnected-(U$8-14.NC-Pad14)") (class "Default")
      (node (ref "U$8") (pin "14") (pinfunction "14.NC_14") (pintype "bidirectional"))
    )
    (net (code "80") (name "unconnected-(U$8-19.INTB-Pad19)") (class "Default")
      (node (ref "U$8") (pin "19") (pinfunction "19.INTB_19") (pintype "bidirectional"))
    )
    (net (code "81") (name "unconnected-(U$8-20.INTA-Pad20)") (class "Default")
      (node (ref "U$8") (pin "20") (pinfunction "20.INTA_20") (pintype "bidirectional"))
    )
    (net (code "82") (name "unconnected-(U$10-7.VM-Pad7)") (class "Default")
      (node (ref "U$10") (pin "7") (pinfunction "7.VM_7") (pintype "bidirectional"))
    )
  )
)
